# Simple_USB_SC_Interface.net
KiCad netlist of a schematic drawn in EAGLE
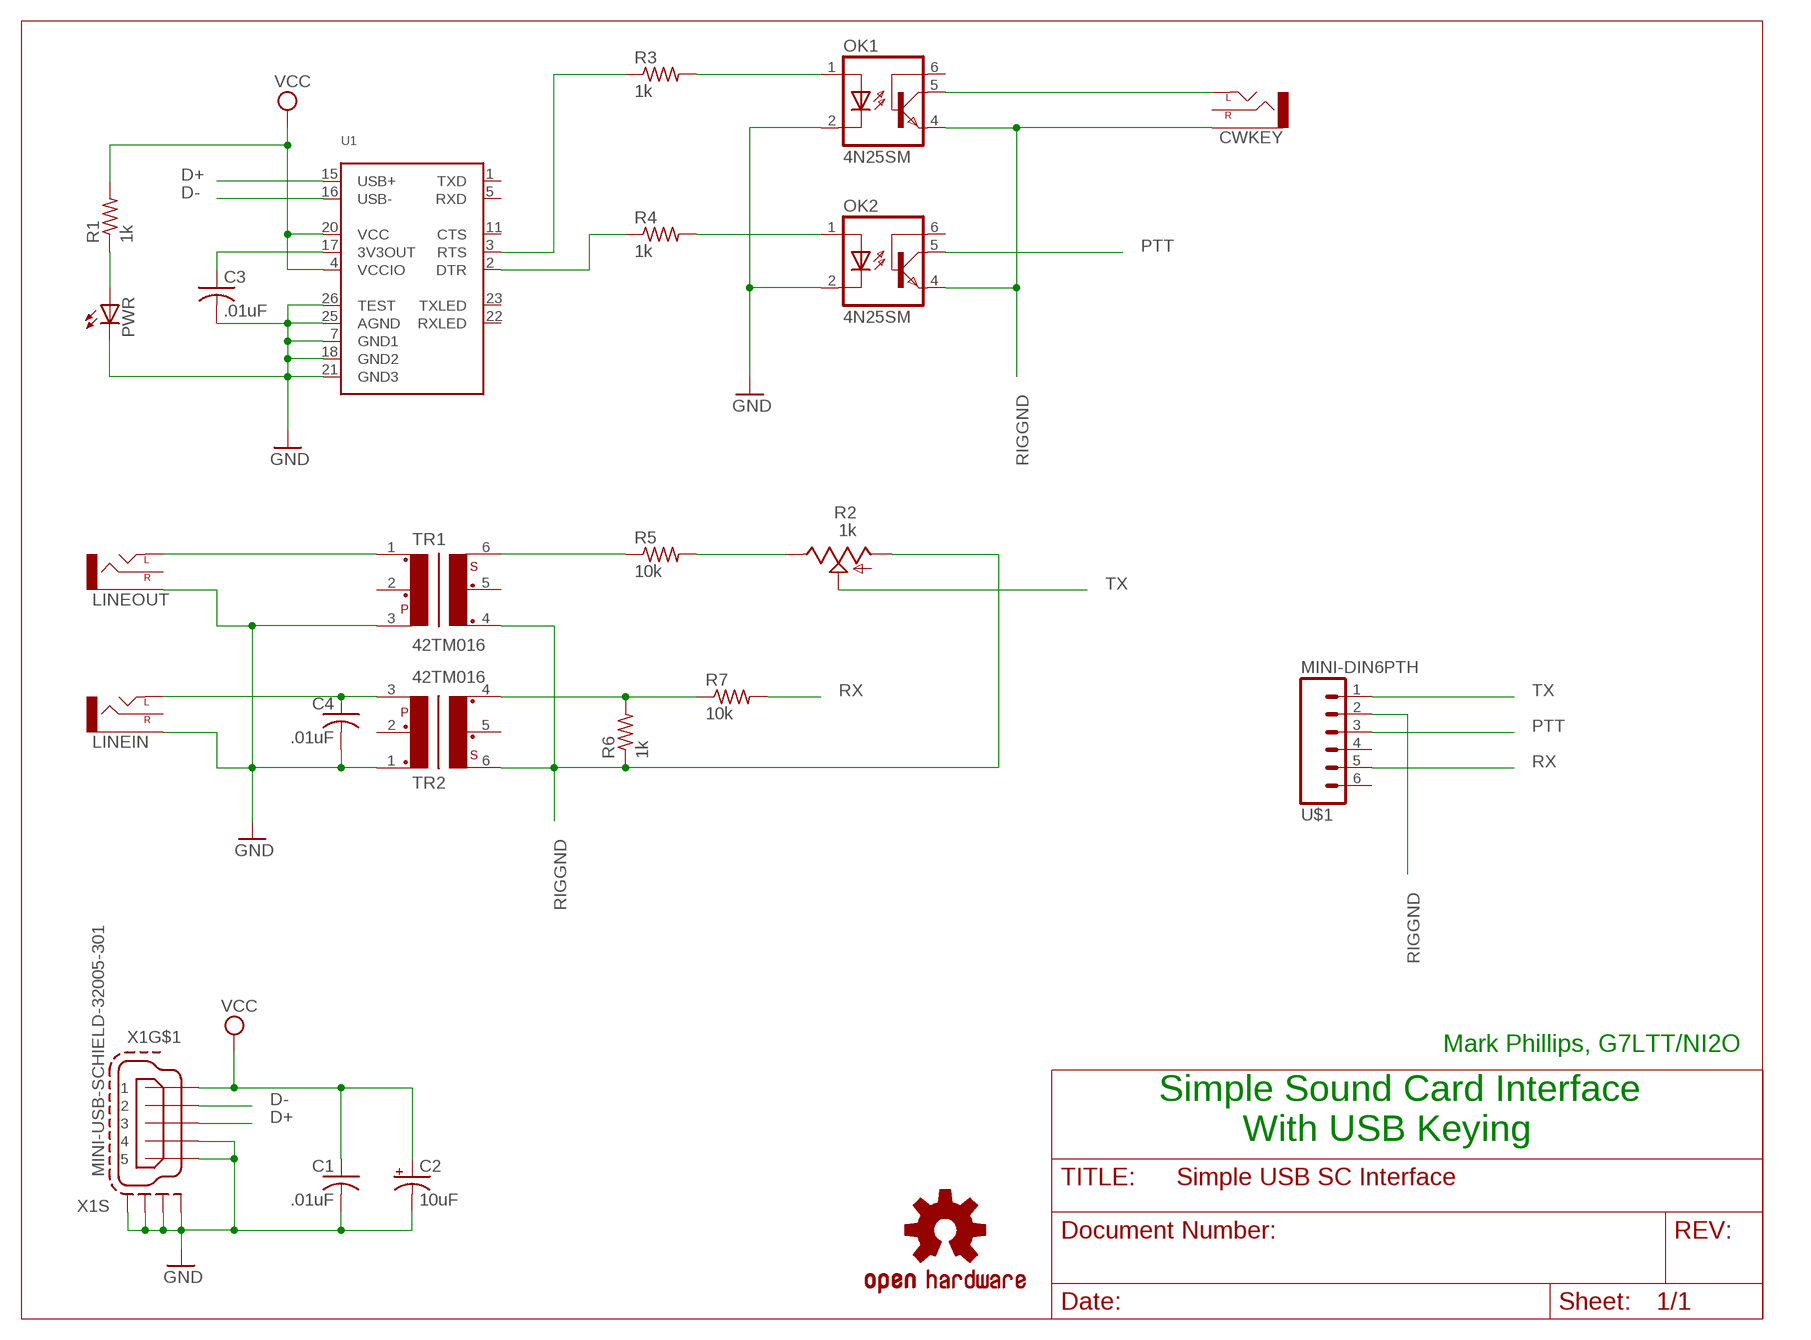
[diagram p0: schematic, sheet 1]

(export (version "E")
  (design (tool "Eeschema 10.0.6"))
  (components
    (comp (ref "C1")
      (value ".01uF")
      (footprint "eagle-import:C0805")
      (libsource (lib "eagle-import") (part "C-USC0805"))
    )
    (comp (ref "C2")
      (value "10uF")
      (footprint "eagle-import:E2,5-5")
      (libsource (lib "eagle-import") (part "CPOL-USE2.5-5"))
    )
    (comp (ref "C3")
      (value ".01uF")
      (footprint "eagle-import:C0805")
      (libsource (lib "eagle-import") (part "C-USC0805"))
    )
    (comp (ref "C4")
      (value ".01uF")
      (footprint "eagle-import:C0805")
      (libsource (lib "eagle-import") (part "C-USC0805"))
    )
    (comp (ref "CWKEY")
      (value "AUDIO-JACKSMD2")
      (footprint "eagle-import:AUDIO-JACK-3.5MM-SMD")
      (libsource (lib "eagle-import") (part "AUDIO-JACKSMD2"))
    )
    (comp (ref "LINEIN")
      (value "AUDIO-JACKSMD2")
      (footprint "eagle-import:AUDIO-JACK-3.5MM-SMD")
      (libsource (lib "eagle-import") (part "AUDIO-JACKSMD2"))
    )
    (comp (ref "LINEOUT")
      (value "AUDIO-JACKSMD2")
      (footprint "eagle-import:AUDIO-JACK-3.5MM-SMD")
      (libsource (lib "eagle-import") (part "AUDIO-JACKSMD2"))
    )
    (comp (ref "LOGO1")
      (value "OSHW-LOGOM")
      (footprint "eagle-import:OSHW-LOGO-M")
      (libsource (lib "eagle-import") (part "OSHW-LOGOM"))
    )
    (comp (ref "OK1")
      (value "4N25SM")
      (footprint "eagle-import:DIL6-SMD")
      (fields (field (name "MF") "FAIRCHILD SEMICONDUCTOR"))
      (libsource (lib "eagle-import") (part "4N?MS25"))
    )
    (comp (ref "OK2")
      (value "4N25SM")
      (footprint "eagle-import:DIL6-SMD")
      (fields (field (name "MF") "FAIRCHILD SEMICONDUCTOR"))
      (libsource (lib "eagle-import") (part "4N?MS25"))
    )
    (comp (ref "PWR")
      (value "LEDCHIP-LED0805")
      (footprint "eagle-import:CHIP-LED0805")
      (libsource (lib "eagle-import") (part "LEDCHIP-LED0805"))
    )
    (comp (ref "R1")
      (value "1k")
      (footprint "eagle-import:M0805")
      (libsource (lib "eagle-import") (part "R-US_M0805"))
    )
    (comp (ref "R2")
      (value "1k")
      (footprint "eagle-import:CA6V")
      (libsource (lib "eagle-import") (part "TRIM_US-CA6V"))
    )
    (comp (ref "R3")
      (value "1k")
      (footprint "eagle-import:M0805")
      (libsource (lib "eagle-import") (part "R-US_M0805"))
    )
    (comp (ref "R4")
      (value "1k")
      (footprint "eagle-import:M0805")
      (libsource (lib "eagle-import") (part "R-US_M0805"))
    )
    (comp (ref "R5")
      (value "10k")
      (footprint "eagle-import:M0805")
      (libsource (lib "eagle-import") (part "R-US_M0805"))
    )
    (comp (ref "R6")
      (value "1k")
      (footprint "eagle-import:M0805")
      (libsource (lib "eagle-import") (part "R-US_M0805"))
    )
    (comp (ref "R7")
      (value "10k")
      (footprint "eagle-import:M0805")
      (libsource (lib "eagle-import") (part "R-US_M0805"))
    )
    (comp (ref "TR1")
      (value "42TM016")
      (footprint "eagle-import:42TM")
      (libsource (lib "eagle-import") (part "42T?M016"))
    )
    (comp (ref "TR2")
      (value "42TM016")
      (footprint "eagle-import:42TM")
      (libsource (lib "eagle-import") (part "42T?M016"))
    )
    (comp (ref "U$1")
      (value "MINI-DIN6PTH")
      (footprint "eagle-import:MINI-DIN6")
      (libsource (lib "eagle-import") (part "MINI-DIN6PTH"))
    )
    (comp (ref "U1")
      (value "FT232RLSSOP28")
      (footprint "eagle-import:SSOP28DB")
      (libsource (lib "eagle-import") (part "FT232RLSSOP28"))
    )
    (comp (ref "X1")
      (value "MINI-USB-SCHIELD-32005-301")
      (footprint "eagle-import:32005-301")
      (libsource (lib "eagle-import") (part "MINI-USB-SCHIELD-32005-301"))
    )
  )
  (nets
    (net (code "1") (name "/D+") (class "Default")
      (node (ref "U1") (pin "15") (pinfunction "USB+_15") (pintype "bidirectional"))
      (node (ref "X1") (pin "3") (pinfunction "3_3") (pintype "passive"))
    )
    (net (code "2") (name "/D-") (class "Default")
      (node (ref "U1") (pin "16") (pinfunction "USB-_16") (pintype "bidirectional"))
      (node (ref "X1") (pin "2") (pinfunction "2_2") (pintype "passive"))
    )
    (net (code "3") (name "/PTT") (class "Default")
      (node (ref "OK2") (pin "5") (pinfunction "COL_5") (pintype "passive"))
      (node (ref "U$1") (pin "3") (pinfunction "3_3") (pintype "passive"))
    )
    (net (code "4") (name "/RIGGND") (class "Default")
      (node (ref "CWKEY") (pin "SLEEVE") (pinfunction "SLEEVE_SLEEVE") (pintype "bidirectional"))
      (node (ref "OK1") (pin "4") (pinfunction "EMI_4") (pintype "passive"))
      (node (ref "OK2") (pin "4") (pinfunction "EMI_4") (pintype "passive"))
      (node (ref "R2") (pin "A") (pinfunction "A_A") (pintype "passive"))
      (node (ref "R6") (pin "1") (pinfunction "1_1") (pintype "passive"))
      (node (ref "TR1") (pin "4") (pinfunction "4_4") (pintype "passive"))
      (node (ref "TR2") (pin "6") (pinfunction "6_6") (pintype "passive"))
      (node (ref "U$1") (pin "2") (pinfunction "2_2") (pintype "passive"))
    )
    (net (code "5") (name "/RX") (class "Default")
      (node (ref "R7") (pin "2") (pinfunction "2_2") (pintype "passive"))
      (node (ref "U$1") (pin "5") (pinfunction "5_5") (pintype "passive"))
    )
    (net (code "6") (name "/TX") (class "Default")
      (node (ref "R2") (pin "S") (pinfunction "S_S") (pintype "passive"))
      (node (ref "U$1") (pin "1") (pinfunction "1_1") (pintype "passive"))
    )
    (net (code "7") (name "GND") (class "Default")
      (node (ref "C1") (pin "2") (pinfunction "2_2") (pintype "passive"))
      (node (ref "C2") (pin "-") (pinfunction "-_-") (pintype "passive"))
      (node (ref "C3") (pin "2") (pinfunction "2_2") (pintype "passive"))
      (node (ref "C4") (pin "2") (pinfunction "2_2") (pintype "passive"))
      (node (ref "LINEIN") (pin "SLEEVE") (pinfunction "SLEEVE_SLEEVE") (pintype "bidirectional"))
      (node (ref "LINEOUT") (pin "SLEEVE") (pinfunction "SLEEVE_SLEEVE") (pintype "bidirectional"))
      (node (ref "OK1") (pin "2") (pinfunction "C_2") (pintype "passive"))
      (node (ref "OK2") (pin "2") (pinfunction "C_2") (pintype "passive"))
      (node (ref "PWR") (pin "C") (pinfunction "C_C") (pintype "passive"))
      (node (ref "TR1") (pin "3") (pinfunction "3_3") (pintype "passive"))
      (node (ref "TR2") (pin "1") (pinfunction "1_1") (pintype "passive"))
      (node (ref "U1") (pin "18") (pinfunction "GND2_18") (pintype "power_in"))
      (node (ref "U1") (pin "21") (pinfunction "GND3_21") (pintype "power_in"))
      (node (ref "U1") (pin "25") (pinfunction "AGND_25") (pintype "power_in"))
      (node (ref "U1") (pin "26") (pinfunction "TEST_26") (pintype "input"))
      (node (ref "U1") (pin "7") (pinfunction "GND1_7") (pintype "power_in"))
      (node (ref "X1") (pin "4") (pinfunction "4_4") (pintype "passive"))
      (node (ref "X1") (pin "5") (pinfunction "5_5") (pintype "passive"))
      (node (ref "X1") (pin "M1") (pinfunction "S1_M1") (pintype "passive"))
      (node (ref "X1") (pin "M2") (pinfunction "S2_M2") (pintype "passive"))
      (node (ref "X1") (pin "M3") (pinfunction "S3_M3") (pintype "passive"))
      (node (ref "X1") (pin "M4") (pinfunction "S4_M4") (pintype "passive"))
    )
    (net (code "8") (name "Net-(CWKEY-LEFT)") (class "Default")
      (node (ref "CWKEY") (pin "TIP") (pinfunction "LEFT_TIP") (pintype "bidirectional"))
      (node (ref "OK1") (pin "5") (pinfunction "COL_5") (pintype "passive"))
    )
    (net (code "9") (name "Net-(LINEIN-LEFT)") (class "Default")
      (node (ref "C4") (pin "1") (pinfunction "1_1") (pintype "passive"))
      (node (ref "LINEIN") (pin "TIP") (pinfunction "LEFT_TIP") (pintype "bidirectional"))
      (node (ref "TR2") (pin "3") (pinfunction "3_3") (pintype "passive"))
    )
    (net (code "10") (name "Net-(LINEOUT-LEFT)") (class "Default")
      (node (ref "LINEOUT") (pin "TIP") (pinfunction "LEFT_TIP") (pintype "bidirectional"))
      (node (ref "TR1") (pin "1") (pinfunction "1_1") (pintype "passive"))
    )
    (net (code "11") (name "Net-(OK1-A)") (class "Default")
      (node (ref "OK1") (pin "1") (pinfunction "A_1") (pintype "passive"))
      (node (ref "R3") (pin "2") (pinfunction "2_2") (pintype "passive"))
    )
    (net (code "12") (name "Net-(OK2-A)") (class "Default")
      (node (ref "OK2") (pin "1") (pinfunction "A_1") (pintype "passive"))
      (node (ref "R4") (pin "2") (pinfunction "2_2") (pintype "passive"))
    )
    (net (code "13") (name "Net-(PWR-PadA)") (class "Default")
      (node (ref "PWR") (pin "A") (pinfunction "A_A") (pintype "passive"))
      (node (ref "R1") (pin "1") (pinfunction "1_1") (pintype "passive"))
    )
    (net (code "14") (name "Net-(R2-PadE)") (class "Default")
      (node (ref "R2") (pin "E") (pinfunction "E_E") (pintype "passive"))
      (node (ref "R5") (pin "2") (pinfunction "2_2") (pintype "passive"))
    )
    (net (code "15") (name "Net-(R5-Pad1)") (class "Default")
      (node (ref "R5") (pin "1") (pinfunction "1_1") (pintype "passive"))
      (node (ref "TR1") (pin "6") (pinfunction "6_6") (pintype "passive"))
    )
    (net (code "16") (name "Net-(R6-Pad2)") (class "Default")
      (node (ref "R6") (pin "2") (pinfunction "2_2") (pintype "passive"))
      (node (ref "R7") (pin "1") (pinfunction "1_1") (pintype "passive"))
      (node (ref "TR2") (pin "4") (pinfunction "4_4") (pintype "passive"))
    )
    (net (code "17") (name "Net-(U1-3V3OUT)") (class "Default")
      (node (ref "C3") (pin "1") (pinfunction "1_1") (pintype "passive"))
      (node (ref "U1") (pin "17") (pinfunction "3V3OUT_17") (pintype "power_in"))
    )
    (net (code "18") (name "Net-(U1-DTR)") (class "Default")
      (node (ref "R4") (pin "1") (pinfunction "1_1") (pintype "passive"))
      (node (ref "U1") (pin "2") (pinfunction "DTR_2") (pintype "bidirectional"))
    )
    (net (code "19") (name "Net-(U1-RTS)") (class "Default")
      (node (ref "R3") (pin "1") (pinfunction "1_1") (pintype "passive"))
      (node (ref "U1") (pin "3") (pinfunction "RTS_3") (pintype "bidirectional"))
    )
    (net (code "20") (name "VCC") (class "Default")
      (node (ref "C1") (pin "1") (pinfunction "1_1") (pintype "passive"))
      (node (ref "C2") (pin "+") (pinfunction "+_+") (pintype "passive"))
      (node (ref "R1") (pin "2") (pinfunction "2_2") (pintype "passive"))
      (node (ref "U1") (pin "20") (pinfunction "VCC_20") (pintype "power_in"))
      (node (ref "U1") (pin "4") (pinfunction "VCCIO_4") (pintype "power_in"))
      (node (ref "X1") (pin "1") (pinfunction "1_1") (pintype "passive"))
    )
    (net (code "21") (name "unconnected-(CWKEY-RIGHT-PadRING)") (class "Default")
      (node (ref "CWKEY") (pin "RING") (pinfunction "RIGHT_RING") (pintype "bidirectional"))
    )
    (net (code "22") (name "unconnected-(LINEIN-RIGHT-PadRING)") (class "Default")
      (node (ref "LINEIN") (pin "RING") (pinfunction "RIGHT_RING") (pintype "bidirectional"))
    )
    (net (code "23") (name "unconnected-(LINEOUT-RIGHT-PadRING)") (class "Default")
      (node (ref "LINEOUT") (pin "RING") (pinfunction "RIGHT_RING") (pintype "bidirectional"))
    )
    (net (code "24") (name "unconnected-(OK1-BAS-Pad6)") (class "Default")
      (node (ref "OK1") (pin "6") (pinfunction "BAS_6") (pintype "passive"))
    )
    (net (code "25") (name "unconnected-(OK2-BAS-Pad6)") (class "Default")
      (node (ref "OK2") (pin "6") (pinfunction "BAS_6") (pintype "passive"))
    )
    (net (code "26") (name "unconnected-(TR1-Pad2)") (class "Default")
      (node (ref "TR1") (pin "2") (pinfunction "2_2") (pintype "passive"))
    )
    (net (code "27") (name "unconnected-(TR1-Pad5)") (class "Default")
      (node (ref "TR1") (pin "5") (pinfunction "5_5") (pintype "passive"))
    )
    (net (code "28") (name "unconnected-(TR2-Pad2)") (class "Default")
      (node (ref "TR2") (pin "2") (pinfunction "2_2") (pintype "passive"))
    )
    (net (code "29") (name "unconnected-(TR2-Pad5)") (class "Default")
      (node (ref "TR2") (pin "5") (pinfunction "5_5") (pintype "passive"))
    )
    (net (code "30") (name "unconnected-(U$1-Pad4)") (class "Default")
      (node (ref "U$1") (pin "4") (pinfunction "4_4") (pintype "passive"))
    )
    (net (code "31") (name "unconnected-(U$1-Pad6)") (class "Default")
      (node (ref "U$1") (pin "6") (pinfunction "6_6") (pintype "passive"))
    )
    (net (code "32") (name "unconnected-(U1-CTS-Pad11)") (class "Default")
      (node (ref "U1") (pin "11") (pinfunction "CTS_11") (pintype "bidirectional"))
    )
    (net (code "33") (name "unconnected-(U1-RXD-Pad5)") (class "Default")
      (node (ref "U1") (pin "5") (pinfunction "RXD_5") (pintype "input"))
    )
    (net (code "34") (name "unconnected-(U1-RXLED-Pad22)") (class "Default")
      (node (ref "U1") (pin "22") (pinfunction "RXLED_22") (pintype "bidirectional"))
    )
    (net (code "35") (name "unconnected-(U1-TXD-Pad1)") (class "Default")
      (node (ref "U1") (pin "1") (pinfunction "TXD_1") (pintype "output"))
    )
    (net (code "36") (name "unconnected-(U1-TXLED-Pad23)") (class "Default")
      (node (ref "U1") (pin "23") (pinfunction "TXLED_23") (pintype "bidirectional"))
    )
  )
)
